# lighting.net
KiCad netlist of a schematic drawn in EAGLE
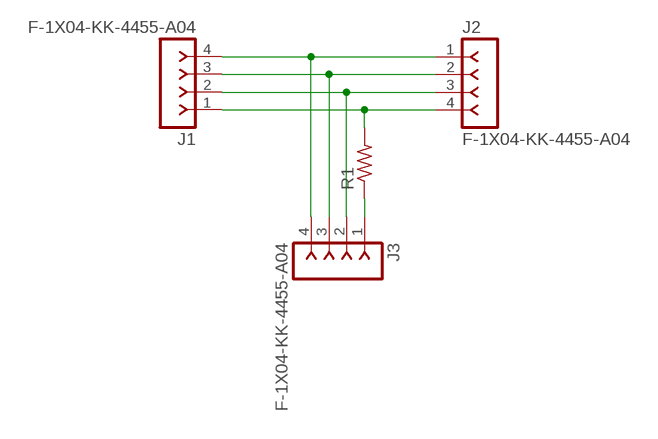
[diagram p0: schematic, sheet 1]

(export (version "E")
  (design (tool "Eeschema 10.0.6"))
  (components
    (comp (ref "J1")
      (value "F-1X04-KK-4455-A04")
      (footprint "eagle-import:KK-4455-A04")
      (libsource (lib "eagle-import") (part "F-1X04-KK-4455-A04"))
    )
    (comp (ref "J2")
      (value "F-1X04-KK-4455-A04")
      (footprint "eagle-import:KK-4455-A04")
      (libsource (lib "eagle-import") (part "F-1X04-KK-4455-A04"))
    )
    (comp (ref "J3")
      (value "F-1X04-KK-4455-A04")
      (footprint "eagle-import:KK-4455-A04")
      (libsource (lib "eagle-import") (part "F-1X04-KK-4455-A04"))
    )
    (comp (ref "R1")
      (value "R-US_0207/12")
      (footprint "eagle-import:0207_12")
      (libsource (lib "eagle-import") (part "R-US_0207/12"))
    )
  )
  (nets
    (net (code "1") (name "Net-(J1-Pad1)") (class "Default")
      (node (ref "J1") (pin "1") (pinfunction "1_1") (pintype "passive"))
      (node (ref "J2") (pin "4") (pinfunction "4_4") (pintype "passive"))
      (node (ref "R1") (pin "2") (pinfunction "2_2") (pintype "passive"))
    )
    (net (code "2") (name "Net-(J1-Pad2)") (class "Default")
      (node (ref "J1") (pin "2") (pinfunction "2_2") (pintype "passive"))
      (node (ref "J2") (pin "3") (pinfunction "3_3") (pintype "passive"))
      (node (ref "J3") (pin "2") (pinfunction "2_2") (pintype "passive"))
    )
    (net (code "3") (name "Net-(J1-Pad3)") (class "Default")
      (node (ref "J1") (pin "3") (pinfunction "3_3") (pintype "passive"))
      (node (ref "J2") (pin "2") (pinfunction "2_2") (pintype "passive"))
      (node (ref "J3") (pin "3") (pinfunction "3_3") (pintype "passive"))
    )
    (net (code "4") (name "Net-(J1-Pad4)") (class "Default")
      (node (ref "J1") (pin "4") (pinfunction "4_4") (pintype "passive"))
      (node (ref "J2") (pin "1") (pinfunction "1_1") (pintype "passive"))
      (node (ref "J3") (pin "4") (pinfunction "4_4") (pintype "passive"))
    )
    (net (code "5") (name "Net-(J3-Pad1)") (class "Default")
      (node (ref "J3") (pin "1") (pinfunction "1_1") (pintype "passive"))
      (node (ref "R1") (pin "1") (pinfunction "1_1") (pintype "passive"))
    )
  )
)
